# SS8400C.net
KiCad netlist of a schematic drawn in Altium Designer
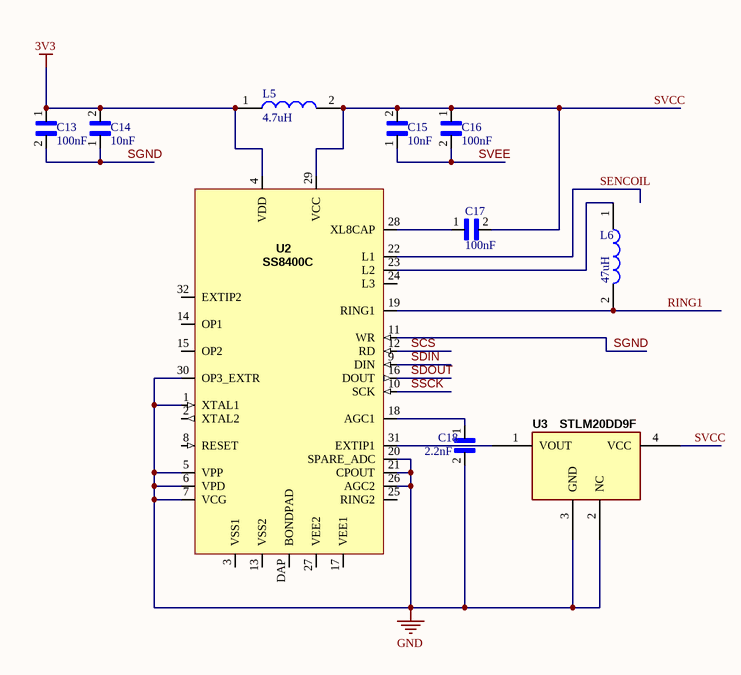
[diagram p0: SS8400C.SchDoc]

(export (version "E")
  (design (tool "Eeschema 10.0.6"))
  (components
    (comp (ref "C13")
      (value "100nF")
      (footprint "CAPC1608X90N")
      (description "0603 100 nF 25 V -20 / +80 % Tolerance Y5V SMT Multilayer Ceramic Capacitor")
      (fields
        (field (name "MANUFACTURER") "Kyocera AVX")
        (field (name "MANUFACTURER PART NUMBER") "06033G104ZAT2A")
      )
      (libsource (lib "") (part "06033G104ZAT2A_1"))
    )
    (comp (ref "C14")
      (value "10nF")
      (footprint "CAPC1608X90N")
      (description "0603 10 nF 50V ±5 % Tolerance X7R Surface Mount Multilayer Ceramic Capacitor")
      (fields
        (field (name "MANUFACTURER") "Kyocera AVX")
        (field (name "MANUFACTURER PART NUMBER") "06035C103JAZ2A")
      )
      (libsource (lib "") (part "06035C103JAZ2A_1"))
    )
    (comp (ref "C15")
      (value "10nF")
      (footprint "CAPC1608X90N")
      (description "0603 10 nF 50V ±5 % Tolerance X7R Surface Mount Multilayer Ceramic Capacitor")
      (fields
        (field (name "MANUFACTURER") "Kyocera AVX")
        (field (name "MANUFACTURER PART NUMBER") "06035C103JAZ2A")
      )
      (libsource (lib "SnapEDA_Library") (part "06035C103JAZ2A"))
    )
    (comp (ref "C16")
      (value "100nF")
      (footprint "CAPC1608X90N")
      (description "0603 100 nF 25 V -20 / +80 % Tolerance Y5V SMT Multilayer Ceramic Capacitor")
      (fields
        (field (name "MANUFACTURER") "Kyocera AVX")
        (field (name "MANUFACTURER PART NUMBER") "06033G104ZAT2A")
      )
      (libsource (lib "") (part "06033G104ZAT2A_2"))
    )
    (comp (ref "C17")
      (value "100nF")
      (footprint "CAPC1608X90N")
      (description "0603 100 nF 25 V -20 / +80 % Tolerance Y5V SMT Multilayer Ceramic Capacitor")
      (fields
        (field (name "MANUFACTURER") "Kyocera AVX")
        (field (name "MANUFACTURER PART NUMBER") "06033G104ZAT2A")
      )
      (libsource (lib "SnapEDA_Library") (part "06033G104ZAT2A"))
    )
    (comp (ref "C18")
      (value "2.2nF")
      (footprint "CAPC1608X90N")
      (description "0603 2.2 nF 50V ±10 % Tolerance X7R Surface Mount Multilayer Ceramic Capacitor")
      (fields
        (field (name "MANUFACTURER") "Kyocera AVX")
        (field (name "MANUFACTURER PART NUMBER") "06035C222KAT2A")
      )
      (libsource (lib "SnapEDA_Library") (part "06035C222KAT2A"))
    )
    (comp (ref "L5")
      (value "4.7uH")
      (footprint "B82498F")
      (description "FIXED IND 4.7UH 90MA 3.8 OHM SMD")
      (fields
        (field (name "MANUFACTURER") "TDK EPCOS")
        (field (name "MANUFACTURER PART NUMBER") "B82498F1472J000")
      )
      (libsource (lib "Flex PCB") (part "B82498F1472J000"))
    )
    (comp (ref "L6")
      (value "47uH")
      (footprint "AISC0805F470GT")
      (description "Inductor RF Wirewound 47uH 2% 2.5MHz 10Q-Factor Ferrite 0.055A 13.8Ohm DCR 0805 T/R")
      (fields
        (field (name "MANUFACTURER") "Abracon")
        (field (name "MANUFACTURER PART NUMBER") "AISC-0805F-470G-T")
      )
      (libsource (lib "Flex PCB") (part "AISC-0805F-470G-T"))
    )
    (comp (ref "U2")
      (value "SS8400C")
      (footprint "SS8400C_WLCSP")
      (libsource (lib "Flex PCB") (part "SS8400-Legacy"))
    )
    (comp (ref "U3")
      (value "STLM20DD9F")
      (footprint "QFN55P130X100X55-4N")
      (description "Ultra-low current 2.4 V precision analog temperature sensor")
      (fields (field (name "MANUFACTURER") "STMicroelectronics"))
      (libsource (lib "Flex PCB") (part "LM20DD9"))
    )
  )
  (nets
    (net (code "1") (name "/RING1") (class "Default")
      (node (ref "L6") (pin "2") (pinfunction "2_2") (pintype "passive"))
      (node (ref "U2") (pin "19") (pinfunction "RING1_19") (pintype "passive"))
    )
    (net (code "2") (name "/SCS") (class "Default")
      (node (ref "U2") (pin "12") (pinfunction "RD_12") (pintype "input"))
    )
    (net (code "3") (name "/SDIN") (class "Default")
      (node (ref "U2") (pin "9") (pinfunction "DIN_9") (pintype "input"))
    )
    (net (code "4") (name "/SDOUT") (class "Default")
      (node (ref "U2") (pin "16") (pinfunction "DOUT_16") (pintype "output"))
    )
    (net (code "5") (name "/SENCOIL") (class "Default")
      (node (ref "U2") (pin "22") (pinfunction "L1_22") (pintype "passive"))
    )
    (net (code "6") (name "/SGND") (class "Default")
      (node (ref "C13") (pin "2") (pinfunction "2_2") (pintype "passive"))
      (node (ref "C14") (pin "1") (pinfunction "1_1") (pintype "passive"))
      (node (ref "U2") (pin "11") (pinfunction "WR_11") (pintype "input"))
    )
    (net (code "7") (name "/SSCK") (class "Default")
      (node (ref "U2") (pin "10") (pinfunction "SCK_10") (pintype "input"))
    )
    (net (code "8") (name "/SVCC") (class "Default")
      (node (ref "C15") (pin "2") (pinfunction "2_2") (pintype "passive"))
      (node (ref "C16") (pin "1") (pinfunction "1_1") (pintype "passive"))
      (node (ref "C17") (pin "2") (pinfunction "2_2") (pintype "passive"))
      (node (ref "L5") (pin "2") (pinfunction "2_2") (pintype "passive"))
      (node (ref "U2") (pin "29") (pinfunction "VCC_29") (pintype "passive"))
      (node (ref "U3") (pin "4") (pinfunction "VCC_4") (pintype "passive"))
    )
    (net (code "9") (name "/SVEE") (class "Default")
      (node (ref "C15") (pin "1") (pinfunction "1_1") (pintype "passive"))
      (node (ref "C16") (pin "2") (pinfunction "2_2") (pintype "passive"))
    )
    (net (code "10") (name "3V3") (class "Default")
      (node (ref "C13") (pin "1") (pinfunction "1_1") (pintype "passive"))
      (node (ref "C14") (pin "2") (pinfunction "2_2") (pintype "passive"))
      (node (ref "L5") (pin "1") (pinfunction "1_1") (pintype "passive"))
      (node (ref "U2") (pin "4") (pinfunction "VDD_4") (pintype "passive"))
    )
    (net (code "11") (name "GND") (class "Default")
      (node (ref "C18") (pin "2") (pinfunction "2_2") (pintype "passive"))
      (node (ref "U2") (pin "1") (pinfunction "XTAL1_1") (pintype "input"))
      (node (ref "U2") (pin "20") (pinfunction "SPARE_ADC_20") (pintype "passive"))
      (node (ref "U2") (pin "21") (pinfunction "CPOUT_21") (pintype "passive"))
      (node (ref "U2") (pin "26") (pinfunction "AGC2_26") (pintype "passive"))
      (node (ref "U2") (pin "30") (pinfunction "OP3_EXTR_30") (pintype "passive"))
      (node (ref "U2") (pin "5") (pinfunction "VPP_5") (pintype "passive"))
      (node (ref "U2") (pin "6") (pinfunction "VPD_6") (pintype "passive"))
      (node (ref "U2") (pin "7") (pinfunction "VCG_7") (pintype "passive"))
      (node (ref "U3") (pin "2") (pinfunction "NC_2") (pintype "passive"))
      (node (ref "U3") (pin "3") (pinfunction "GND_3") (pintype "passive"))
    )
    (net (code "12") (name "Net-(U2-AGC1)") (class "Default")
      (node (ref "C18") (pin "1") (pinfunction "1_1") (pintype "passive"))
      (node (ref "U2") (pin "18") (pinfunction "AGC1_18") (pintype "passive"))
    )
    (net (code "13") (name "Net-(U2-EXTIP1)") (class "Default")
      (node (ref "U2") (pin "31") (pinfunction "EXTIP1_31") (pintype "passive"))
      (node (ref "U3") (pin "1") (pinfunction "VOUT_1") (pintype "passive"))
    )
    (net (code "14") (name "Net-(U2-L2)") (class "Default")
      (node (ref "L6") (pin "1") (pinfunction "1_1") (pintype "passive"))
      (node (ref "U2") (pin "23") (pinfunction "L2_23") (pintype "passive"))
    )
    (net (code "15") (name "Net-(U2-XL8CAP)") (class "Default")
      (node (ref "C17") (pin "1") (pinfunction "1_1") (pintype "passive"))
      (node (ref "U2") (pin "28") (pinfunction "XL8CAP_28") (pintype "passive"))
    )
    (net (code "16") (name "unconnected-(U2-BONDPAD-PadDAP)") (class "Default")
      (node (ref "U2") (pin "DAP") (pinfunction "BONDPAD_DAP") (pintype "passive"))
    )
    (net (code "17") (name "unconnected-(U2-EXTIP2-Pad32)") (class "Default")
      (node (ref "U2") (pin "32") (pinfunction "EXTIP2_32") (pintype "passive"))
    )
    (net (code "18") (name "unconnected-(U2-L3-Pad24)") (class "Default")
      (node (ref "U2") (pin "24") (pinfunction "L3_24") (pintype "passive"))
    )
    (net (code "19") (name "unconnected-(U2-OP1-Pad14)") (class "Default")
      (node (ref "U2") (pin "14") (pinfunction "OP1_14") (pintype "passive"))
    )
    (net (code "20") (name "unconnected-(U2-OP2-Pad15)") (class "Default")
      (node (ref "U2") (pin "15") (pinfunction "OP2_15") (pintype "passive"))
    )
    (net (code "21") (name "unconnected-(U2-RESET-Pad8)") (class "Default")
      (node (ref "U2") (pin "8") (pinfunction "RESET_8") (pintype "input"))
    )
    (net (code "22") (name "unconnected-(U2-RING2-Pad25)") (class "Default")
      (node (ref "U2") (pin "25") (pinfunction "RING2_25") (pintype "passive"))
    )
    (net (code "23") (name "unconnected-(U2-VEE1-Pad17)") (class "Default")
      (node (ref "U2") (pin "17") (pinfunction "VEE1_17") (pintype "passive"))
    )
    (net (code "24") (name "unconnected-(U2-VEE2-Pad27)") (class "Default")
      (node (ref "U2") (pin "27") (pinfunction "VEE2_27") (pintype "passive"))
    )
    (net (code "25") (name "unconnected-(U2-VSS1-Pad3)") (class "Default")
      (node (ref "U2") (pin "3") (pinfunction "VSS1_3") (pintype "passive"))
    )
    (net (code "26") (name "unconnected-(U2-VSS2-Pad13)") (class "Default")
      (node (ref "U2") (pin "13") (pinfunction "VSS2_13") (pintype "passive"))
    )
    (net (code "27") (name "unconnected-(U2-XTAL2-Pad2)") (class "Default")
      (node (ref "U2") (pin "2") (pinfunction "XTAL2_2") (pintype "output"))
    )
  )
)
